# freq-gen.net
KiCad netlist of a schematic drawn in EAGLE
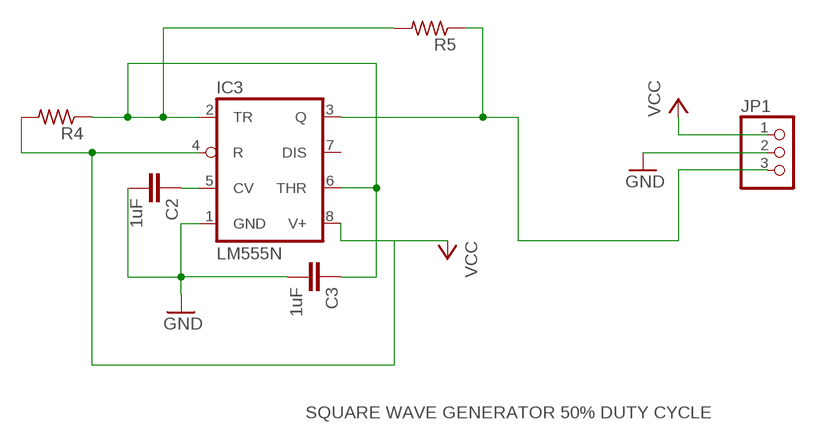
[diagram p0: schematic, sheet 1]

(export (version "E")
  (design (tool "Eeschema 10.0.6"))
  (components
    (comp (ref "C2")
      (value "1uF")
      (footprint "eagle-import:C2.5-3")
      (libsource (lib "eagle-import") (part "C2,5-3"))
    )
    (comp (ref "C3")
      (value "1uF")
      (footprint "eagle-import:C2.5-3")
      (libsource (lib "eagle-import") (part "C2,5-3"))
    )
    (comp (ref "IC3")
      (value "LM555N")
      (footprint "eagle-import:DIL08-ROUND")
      (libsource (lib "eagle-import") (part "555NLM"))
    )
    (comp (ref "JP1")
      (value "PINHD-1X3")
      (footprint "eagle-import:1X03")
      (libsource (lib "eagle-import") (part "PINHD-1X3"))
    )
    (comp (ref "R4")
      (value "R-US_0204/7")
      (footprint "eagle-import:0204_7")
      (libsource (lib "eagle-import") (part "R-US_0204/7"))
    )
    (comp (ref "R5")
      (value "R-US_0204/7")
      (footprint "eagle-import:0204_7")
      (libsource (lib "eagle-import") (part "R-US_0204/7"))
    )
  )
  (nets
    (net (code "1") (name "GND") (class "Default")
      (node (ref "C2") (pin "2") (pinfunction "2_2") (pintype "passive"))
      (node (ref "C3") (pin "2") (pinfunction "2_2") (pintype "passive"))
      (node (ref "IC3") (pin "1") (pinfunction "GND_1") (pintype "power_in"))
      (node (ref "JP1") (pin "2") (pinfunction "2_2") (pintype "passive"))
    )
    (net (code "2") (name "Net-(IC3-CV)") (class "Default")
      (node (ref "C2") (pin "1") (pinfunction "1_1") (pintype "passive"))
      (node (ref "IC3") (pin "5") (pinfunction "CV_5") (pintype "input"))
    )
    (net (code "3") (name "Net-(IC3-Q)") (class "Default")
      (node (ref "IC3") (pin "3") (pinfunction "Q_3") (pintype "output"))
      (node (ref "JP1") (pin "3") (pinfunction "3_3") (pintype "passive"))
      (node (ref "R5") (pin "1") (pinfunction "1_1") (pintype "passive"))
    )
    (net (code "4") (name "Net-(IC3-THR)") (class "Default")
      (node (ref "C3") (pin "1") (pinfunction "1_1") (pintype "passive"))
      (node (ref "IC3") (pin "2") (pinfunction "TR_2") (pintype "input"))
      (node (ref "IC3") (pin "6") (pinfunction "THR_6") (pintype "input"))
      (node (ref "R4") (pin "1") (pinfunction "1_1") (pintype "passive"))
      (node (ref "R5") (pin "2") (pinfunction "2_2") (pintype "passive"))
    )
    (net (code "5") (name "VCC") (class "Default")
      (node (ref "IC3") (pin "4") (pinfunction "R_4") (pintype "input"))
      (node (ref "IC3") (pin "8") (pinfunction "V+_8") (pintype "power_in"))
      (node (ref "JP1") (pin "1") (pinfunction "1_1") (pintype "passive"))
      (node (ref "R4") (pin "2") (pinfunction "2_2") (pintype "passive"))
    )
    (net (code "6") (name "unconnected-(IC3-DIS-Pad7)") (class "Default")
      (node (ref "IC3") (pin "7") (pinfunction "DIS_7") (pintype "input"))
    )
  )
)
